# filament.net
KiCad netlist of a schematic drawn in EAGLE
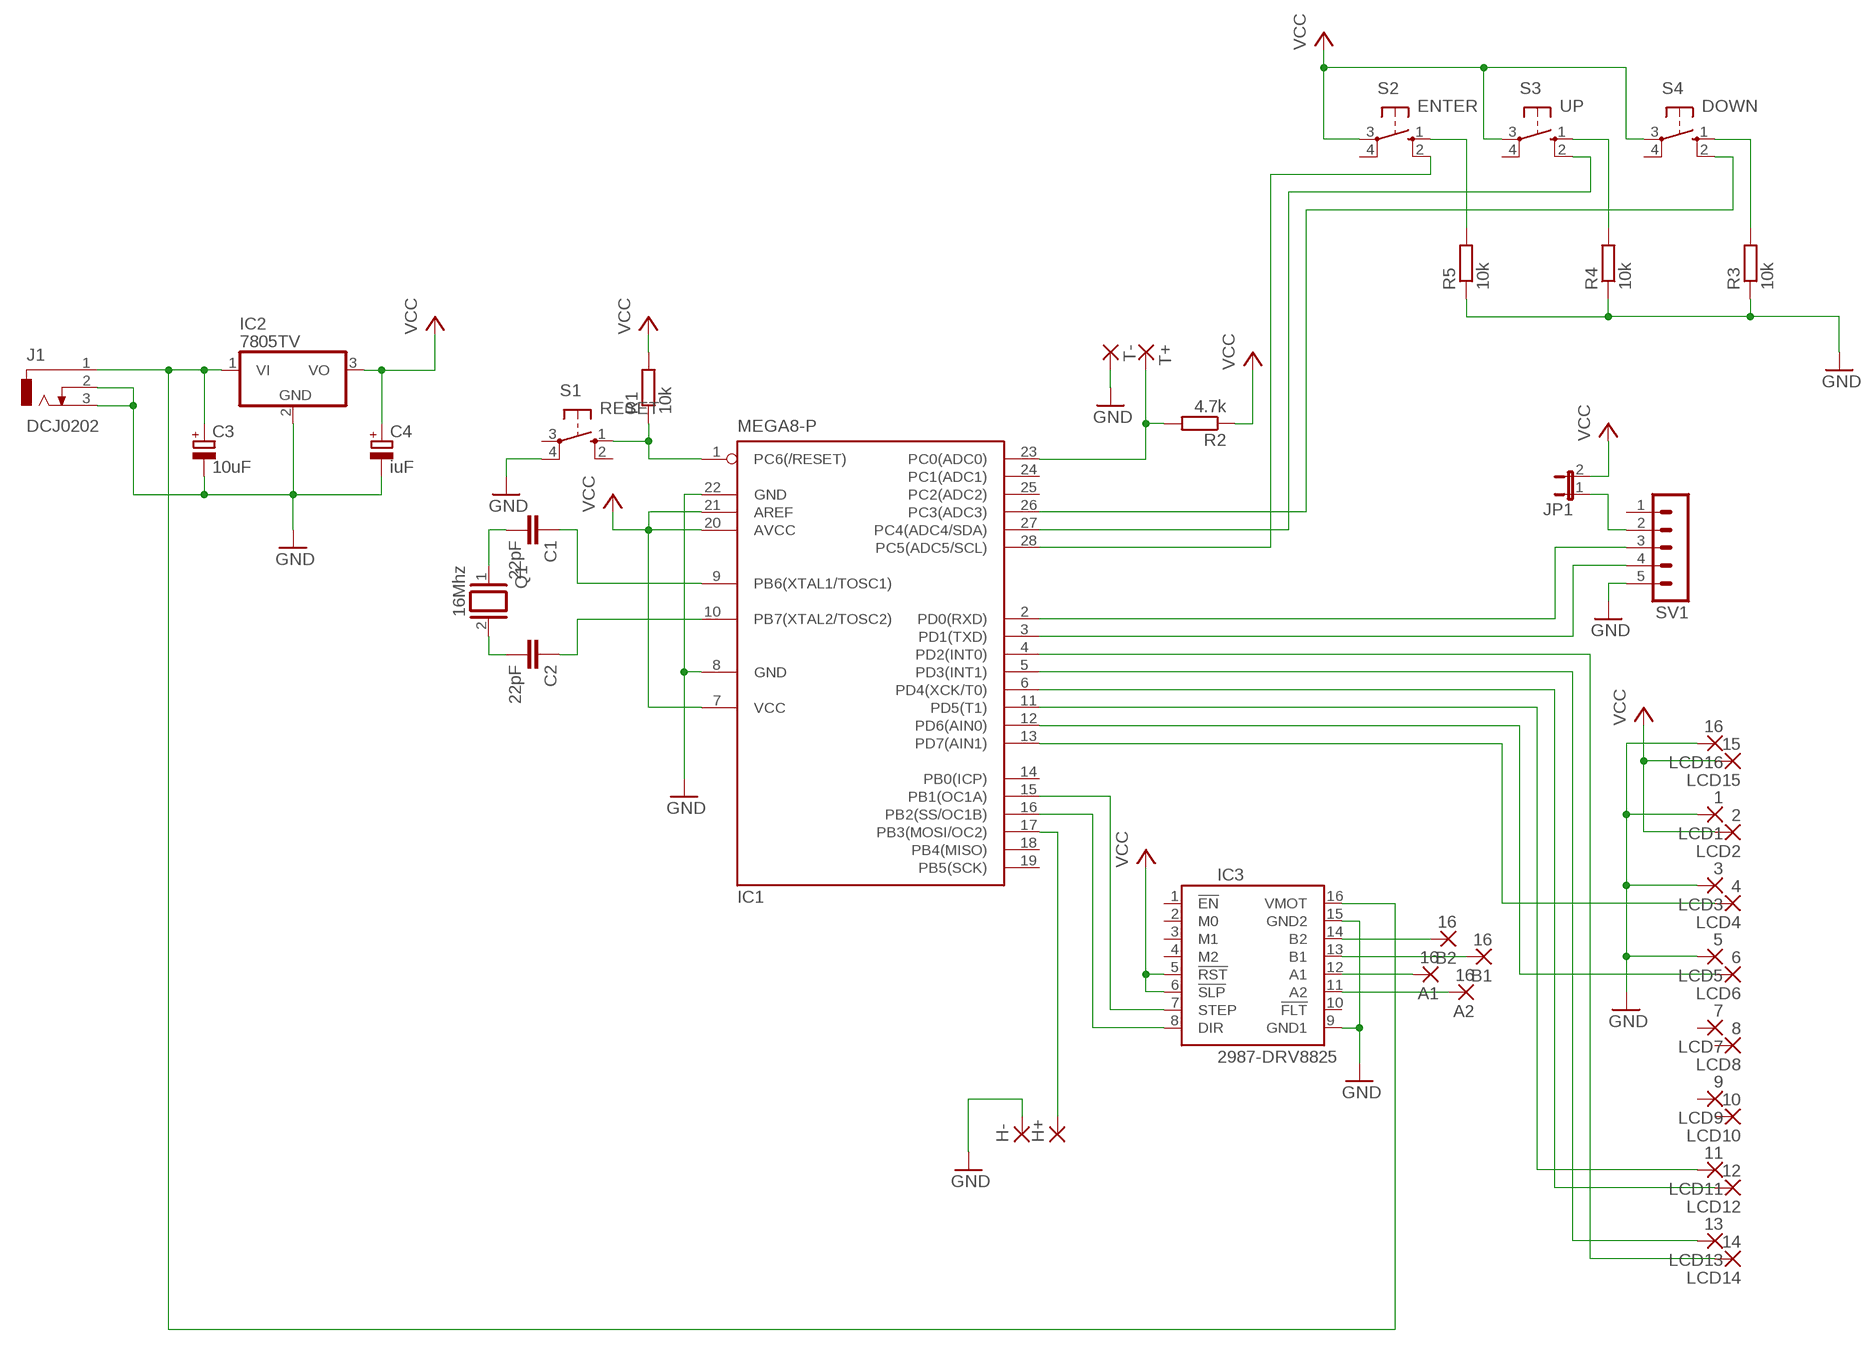
[diagram p0: schematic, sheet 1]

(export (version "E")
  (design (tool "Eeschema 10.0.6"))
  (components
    (comp (ref "A1")
      (value "16")
      (footprint "eagle-import:1,6_0,8")
      (libsource (lib "eagle-import") (part "1,6/0,8"))
    )
    (comp (ref "A2")
      (value "16")
      (footprint "eagle-import:1,6_0,8")
      (libsource (lib "eagle-import") (part "1,6/0,8"))
    )
    (comp (ref "B1")
      (value "16")
      (footprint "eagle-import:1,6_0,8")
      (libsource (lib "eagle-import") (part "1,6/0,8"))
    )
    (comp (ref "B2")
      (value "16")
      (footprint "eagle-import:1,6_0,8")
      (libsource (lib "eagle-import") (part "1,6/0,8"))
    )
    (comp (ref "C1")
      (value "22pF")
      (footprint "eagle-import:C050-025X075")
      (libsource (lib "eagle-import") (part "C-EU050-025X075"))
    )
    (comp (ref "C2")
      (value "22pF")
      (footprint "eagle-import:C050-025X075")
      (libsource (lib "eagle-import") (part "C-EU050-025X075"))
    )
    (comp (ref "C3")
      (value "10uF")
      (footprint "eagle-import:E2-5")
      (libsource (lib "eagle-import") (part "CPOL-EUE2-5"))
    )
    (comp (ref "C4")
      (value "iuF")
      (footprint "eagle-import:E2-5")
      (libsource (lib "eagle-import") (part "CPOL-EUE2-5"))
    )
    (comp (ref "H+")
      (value "1,6/0,8")
      (footprint "eagle-import:1,6_0,8")
      (libsource (lib "eagle-import") (part "1,6/0,8"))
    )
    (comp (ref "H-")
      (value "1,6/0,8")
      (footprint "eagle-import:1,6_0,8")
      (libsource (lib "eagle-import") (part "1,6/0,8"))
    )
    (comp (ref "IC1")
      (value "MEGA8-P")
      (footprint "eagle-import:DIL28-3")
      (libsource (lib "eagle-import") (part "MEGA8-P"))
    )
    (comp (ref "IC2")
      (value "7805TV")
      (footprint "eagle-import:TO220V")
      (libsource (lib "eagle-import") (part "78TV05"))
    )
    (comp (ref "IC3")
      (value "2987-DRV8825")
      (footprint "eagle-import:DRV8825")
      (libsource (lib "eagle-import") (part "2987-DRV8825"))
    )
    (comp (ref "J1")
      (value "DCJ0202")
      (footprint "eagle-import:DCJ0202")
      (libsource (lib "eagle-import") (part "DCJ0202"))
    )
    (comp (ref "JP1")
      (value "JP1E")
      (footprint "eagle-import:JP1")
      (libsource (lib "eagle-import") (part "JP1E"))
    )
    (comp (ref "LCD1")
      (value "1")
      (footprint "eagle-import:1,6_0,8")
      (libsource (lib "eagle-import") (part "1,6/0,8"))
    )
    (comp (ref "LCD2")
      (value "2")
      (footprint "eagle-import:1,6_0,8")
      (libsource (lib "eagle-import") (part "1,6/0,8"))
    )
    (comp (ref "LCD3")
      (value "3")
      (footprint "eagle-import:1,6_0,8")
      (libsource (lib "eagle-import") (part "1,6/0,8"))
    )
    (comp (ref "LCD4")
      (value "4")
      (footprint "eagle-import:1,6_0,8")
      (libsource (lib "eagle-import") (part "1,6/0,8"))
    )
    (comp (ref "LCD5")
      (value "5")
      (footprint "eagle-import:1,6_0,8")
      (libsource (lib "eagle-import") (part "1,6/0,8"))
    )
    (comp (ref "LCD6")
      (value "6")
      (footprint "eagle-import:1,6_0,8")
      (libsource (lib "eagle-import") (part "1,6/0,8"))
    )
    (comp (ref "LCD7")
      (value "7")
      (footprint "eagle-import:1,6_0,8")
      (libsource (lib "eagle-import") (part "1,6/0,8"))
    )
    (comp (ref "LCD8")
      (value "8")
      (footprint "eagle-import:1,6_0,8")
      (libsource (lib "eagle-import") (part "1,6/0,8"))
    )
    (comp (ref "LCD9")
      (value "9")
      (footprint "eagle-import:1,6_0,8")
      (libsource (lib "eagle-import") (part "1,6/0,8"))
    )
    (comp (ref "LCD10")
      (value "10")
      (footprint "eagle-import:1,6_0,8")
      (libsource (lib "eagle-import") (part "1,6/0,8"))
    )
    (comp (ref "LCD11")
      (value "11")
      (footprint "eagle-import:1,6_0,8")
      (libsource (lib "eagle-import") (part "1,6/0,8"))
    )
    (comp (ref "LCD12")
      (value "12")
      (footprint "eagle-import:1,6_0,8")
      (libsource (lib "eagle-import") (part "1,6/0,8"))
    )
    (comp (ref "LCD13")
      (value "13")
      (footprint "eagle-import:1,6_0,8")
      (libsource (lib "eagle-import") (part "1,6/0,8"))
    )
    (comp (ref "LCD14")
      (value "14")
      (footprint "eagle-import:1,6_0,8")
      (libsource (lib "eagle-import") (part "1,6/0,8"))
    )
    (comp (ref "LCD15")
      (value "15")
      (footprint "eagle-import:1,6_0,8")
      (libsource (lib "eagle-import") (part "1,6/0,8"))
    )
    (comp (ref "LCD16")
      (value "16")
      (footprint "eagle-import:1,6_0,8")
      (libsource (lib "eagle-import") (part "1,6/0,8"))
    )
    (comp (ref "Q1")
      (value "16Mhz")
      (footprint "eagle-import:QS")
      (libsource (lib "eagle-import") (part "XTAL/S"))
    )
    (comp (ref "R1")
      (value "10k")
      (footprint "eagle-import:0207_10")
      (libsource (lib "eagle-import") (part "R-EU_0207/10"))
    )
    (comp (ref "R2")
      (value "4.7k")
      (footprint "eagle-import:0207_10")
      (libsource (lib "eagle-import") (part "R-EU_0207/10"))
    )
    (comp (ref "R3")
      (value "10k")
      (footprint "eagle-import:0207_10")
      (libsource (lib "eagle-import") (part "R-EU_0207/10"))
    )
    (comp (ref "R4")
      (value "10k")
      (footprint "eagle-import:0207_10")
      (libsource (lib "eagle-import") (part "R-EU_0207/10"))
    )
    (comp (ref "R5")
      (value "10k")
      (footprint "eagle-import:0207_10")
      (libsource (lib "eagle-import") (part "R-EU_0207/10"))
    )
    (comp (ref "S1")
      (value "RESET")
      (footprint "eagle-import:B3F-10XX")
      (libsource (lib "eagle-import") (part "10-XX"))
    )
    (comp (ref "S2")
      (value "ENTER")
      (footprint "eagle-import:B3F-10XX")
      (libsource (lib "eagle-import") (part "10-XX"))
    )
    (comp (ref "S3")
      (value "UP")
      (footprint "eagle-import:B3F-10XX")
      (libsource (lib "eagle-import") (part "10-XX"))
    )
    (comp (ref "S4")
      (value "DOWN")
      (footprint "eagle-import:B3F-10XX")
      (libsource (lib "eagle-import") (part "10-XX"))
    )
    (comp (ref "SV1")
      (value "MA05-1")
      (footprint "eagle-import:MA05-1")
      (libsource (lib "eagle-import") (part "MA05-1"))
    )
    (comp (ref "T+")
      (value "1,6/0,8")
      (footprint "eagle-import:1,6_0,8")
      (libsource (lib "eagle-import") (part "1,6/0,8"))
    )
    (comp (ref "T-")
      (value "1,6/0,8")
      (footprint "eagle-import:1,6_0,8")
      (libsource (lib "eagle-import") (part "1,6/0,8"))
    )
  )
  (nets
    (net (code "1") (name "GND") (class "Default")
      (node (ref "C3") (pin "-") (pinfunction "-_-") (pintype "passive"))
      (node (ref "C4") (pin "-") (pinfunction "-_-") (pintype "passive"))
      (node (ref "H-") (pin "1") (pinfunction "P_1") (pintype "passive"))
      (node (ref "IC1") (pin "22") (pinfunction "GND_22") (pintype "power_in"))
      (node (ref "IC1") (pin "8") (pinfunction "GND_8") (pintype "power_in"))
      (node (ref "IC2") (pin "2") (pinfunction "GND_2") (pintype "passive"))
      (node (ref "IC3") (pin "15") (pinfunction "GND2_15") (pintype "power_in"))
      (node (ref "IC3") (pin "9") (pinfunction "GND1_9") (pintype "power_in"))
      (node (ref "J1") (pin "2") (pinfunction "2_2") (pintype "passive"))
      (node (ref "J1") (pin "3") (pinfunction "3_3") (pintype "passive"))
      (node (ref "LCD1") (pin "1") (pinfunction "P_1") (pintype "passive"))
      (node (ref "LCD16") (pin "1") (pinfunction "P_1") (pintype "passive"))
      (node (ref "LCD3") (pin "1") (pinfunction "P_1") (pintype "passive"))
      (node (ref "LCD5") (pin "1") (pinfunction "P_1") (pintype "passive"))
      (node (ref "R3") (pin "1") (pinfunction "1_1") (pintype "passive"))
      (node (ref "R4") (pin "1") (pinfunction "1_1") (pintype "passive"))
      (node (ref "R5") (pin "1") (pinfunction "1_1") (pintype "passive"))
      (node (ref "S1") (pin "4") (pinfunction "P1_4") (pintype "passive"))
      (node (ref "SV1") (pin "5") (pinfunction "5_5") (pintype "passive"))
      (node (ref "T-") (pin "1") (pinfunction "P_1") (pintype "passive"))
    )
    (net (code "2") (name "Net-(A1-P)") (class "Default")
      (node (ref "A1") (pin "1") (pinfunction "P_1") (pintype "passive"))
      (node (ref "IC3") (pin "12") (pinfunction "A1_12") (pintype "output"))
    )
    (net (code "3") (name "Net-(A2-P)") (class "Default")
      (node (ref "A2") (pin "1") (pinfunction "P_1") (pintype "passive"))
      (node (ref "IC3") (pin "11") (pinfunction "A2_11") (pintype "output"))
    )
    (net (code "4") (name "Net-(B1-P)") (class "Default")
      (node (ref "B1") (pin "1") (pinfunction "P_1") (pintype "passive"))
      (node (ref "IC3") (pin "13") (pinfunction "B1_13") (pintype "output"))
    )
    (net (code "5") (name "Net-(B2-P)") (class "Default")
      (node (ref "B2") (pin "1") (pinfunction "P_1") (pintype "passive"))
      (node (ref "IC3") (pin "14") (pinfunction "B2_14") (pintype "output"))
    )
    (net (code "6") (name "Net-(C1-Pad2)") (class "Default")
      (node (ref "C1") (pin "2") (pinfunction "2_2") (pintype "passive"))
      (node (ref "Q1") (pin "1") (pinfunction "1_1") (pintype "passive"))
    )
    (net (code "7") (name "Net-(C2-Pad2)") (class "Default")
      (node (ref "C2") (pin "2") (pinfunction "2_2") (pintype "passive"))
      (node (ref "Q1") (pin "2") (pinfunction "2_2") (pintype "passive"))
    )
    (net (code "8") (name "Net-(H+-P)") (class "Default")
      (node (ref "H+") (pin "1") (pinfunction "P_1") (pintype "passive"))
      (node (ref "IC1") (pin "17") (pinfunction "PB3(MOSI/OC2)_17") (pintype "bidirectional"))
    )
    (net (code "9") (name "Net-(IC1-PB1(OC1A))") (class "Default")
      (node (ref "IC1") (pin "15") (pinfunction "PB1(OC1A)_15") (pintype "bidirectional"))
      (node (ref "IC3") (pin "7") (pinfunction "STEP_7") (pintype "input"))
    )
    (net (code "10") (name "Net-(IC1-PB2(SS{slash}OC1B))") (class "Default")
      (node (ref "IC1") (pin "16") (pinfunction "PB2(SS/OC1B)_16") (pintype "bidirectional"))
      (node (ref "IC3") (pin "8") (pinfunction "DIR_8") (pintype "input"))
    )
    (net (code "11") (name "Net-(IC1-PB6(XTAL1{slash}TOSC1))") (class "Default")
      (node (ref "C1") (pin "1") (pinfunction "1_1") (pintype "passive"))
      (node (ref "IC1") (pin "9") (pinfunction "PB6(XTAL1/TOSC1)_9") (pintype "bidirectional"))
    )
    (net (code "12") (name "Net-(IC1-PB7(XTAL2{slash}TOSC2))") (class "Default")
      (node (ref "C2") (pin "1") (pinfunction "1_1") (pintype "passive"))
      (node (ref "IC1") (pin "10") (pinfunction "PB7(XTAL2/TOSC2)_10") (pintype "bidirectional"))
    )
    (net (code "13") (name "Net-(IC1-PC0(ADC0))") (class "Default")
      (node (ref "IC1") (pin "23") (pinfunction "PC0(ADC0)_23") (pintype "bidirectional"))
      (node (ref "R2") (pin "2") (pinfunction "2_2") (pintype "passive"))
      (node (ref "T+") (pin "1") (pinfunction "P_1") (pintype "passive"))
    )
    (net (code "14") (name "Net-(IC1-PC3(ADC3))") (class "Default")
      (node (ref "IC1") (pin "26") (pinfunction "PC3(ADC3)_26") (pintype "bidirectional"))
      (node (ref "S4") (pin "2") (pinfunction "S1_2") (pintype "passive"))
    )
    (net (code "15") (name "Net-(IC1-PC4(ADC4{slash}SDA))") (class "Default")
      (node (ref "IC1") (pin "27") (pinfunction "PC4(ADC4/SDA)_27") (pintype "bidirectional"))
      (node (ref "S3") (pin "2") (pinfunction "S1_2") (pintype "passive"))
    )
    (net (code "16") (name "Net-(IC1-PC5(ADC5{slash}SCL))") (class "Default")
      (node (ref "IC1") (pin "28") (pinfunction "PC5(ADC5/SCL)_28") (pintype "bidirectional"))
      (node (ref "S2") (pin "2") (pinfunction "S1_2") (pintype "passive"))
    )
    (net (code "17") (name "Net-(IC1-PC6({slash}RESET))") (class "Default")
      (node (ref "IC1") (pin "1") (pinfunction "PC6(/RESET)_1") (pintype "bidirectional"))
      (node (ref "R1") (pin "1") (pinfunction "1_1") (pintype "passive"))
      (node (ref "S1") (pin "1") (pinfunction "S_1") (pintype "passive"))
    )
    (net (code "18") (name "Net-(IC1-PD0(RXD))") (class "Default")
      (node (ref "IC1") (pin "2") (pinfunction "PD0(RXD)_2") (pintype "bidirectional"))
      (node (ref "SV1") (pin "3") (pinfunction "3_3") (pintype "passive"))
    )
    (net (code "19") (name "Net-(IC1-PD1(TXD))") (class "Default")
      (node (ref "IC1") (pin "3") (pinfunction "PD1(TXD)_3") (pintype "bidirectional"))
      (node (ref "SV1") (pin "4") (pinfunction "4_4") (pintype "passive"))
    )
    (net (code "20") (name "Net-(IC1-PD2(INT0))") (class "Default")
      (node (ref "IC1") (pin "4") (pinfunction "PD2(INT0)_4") (pintype "bidirectional"))
      (node (ref "LCD14") (pin "1") (pinfunction "P_1") (pintype "passive"))
    )
    (net (code "21") (name "Net-(IC1-PD3(INT1))") (class "Default")
      (node (ref "IC1") (pin "5") (pinfunction "PD3(INT1)_5") (pintype "bidirectional"))
      (node (ref "LCD13") (pin "1") (pinfunction "P_1") (pintype "passive"))
    )
    (net (code "22") (name "Net-(IC1-PD4(XCK{slash}T0))") (class "Default")
      (node (ref "IC1") (pin "6") (pinfunction "PD4(XCK/T0)_6") (pintype "bidirectional"))
      (node (ref "LCD12") (pin "1") (pinfunction "P_1") (pintype "passive"))
    )
    (net (code "23") (name "Net-(IC1-PD5(T1))") (class "Default")
      (node (ref "IC1") (pin "11") (pinfunction "PD5(T1)_11") (pintype "bidirectional"))
      (node (ref "LCD11") (pin "1") (pinfunction "P_1") (pintype "passive"))
    )
    (net (code "24") (name "Net-(IC1-PD6(AIN0))") (class "Default")
      (node (ref "IC1") (pin "12") (pinfunction "PD6(AIN0)_12") (pintype "bidirectional"))
      (node (ref "LCD6") (pin "1") (pinfunction "P_1") (pintype "passive"))
    )
    (net (code "25") (name "Net-(IC1-PD7(AIN1))") (class "Default")
      (node (ref "IC1") (pin "13") (pinfunction "PD7(AIN1)_13") (pintype "bidirectional"))
      (node (ref "LCD4") (pin "1") (pinfunction "P_1") (pintype "passive"))
    )
    (net (code "26") (name "Net-(IC2-VI)") (class "Default")
      (node (ref "C3") (pin "+") (pinfunction "+_+") (pintype "passive"))
      (node (ref "IC2") (pin "1") (pinfunction "VI_1") (pintype "input"))
      (node (ref "IC3") (pin "16") (pinfunction "VMOT_16") (pintype "power_in"))
      (node (ref "J1") (pin "1") (pinfunction "1_1") (pintype "passive"))
    )
    (net (code "27") (name "Net-(JP1-Pad1)") (class "Default")
      (node (ref "JP1") (pin "1") (pinfunction "1_1") (pintype "passive"))
      (node (ref "SV1") (pin "2") (pinfunction "2_2") (pintype "passive"))
    )
    (net (code "28") (name "Net-(S2-S)") (class "Default")
      (node (ref "R5") (pin "2") (pinfunction "2_2") (pintype "passive"))
      (node (ref "S2") (pin "1") (pinfunction "S_1") (pintype "passive"))
    )
    (net (code "29") (name "Net-(S3-S)") (class "Default")
      (node (ref "R4") (pin "2") (pinfunction "2_2") (pintype "passive"))
      (node (ref "S3") (pin "1") (pinfunction "S_1") (pintype "passive"))
    )
    (net (code "30") (name "Net-(S4-S)") (class "Default")
      (node (ref "R3") (pin "2") (pinfunction "2_2") (pintype "passive"))
      (node (ref "S4") (pin "1") (pinfunction "S_1") (pintype "passive"))
    )
    (net (code "31") (name "VCC") (class "Default")
      (node (ref "C4") (pin "+") (pinfunction "+_+") (pintype "passive"))
      (node (ref "IC1") (pin "20") (pinfunction "AVCC_20") (pintype "power_in"))
      (node (ref "IC1") (pin "21") (pinfunction "AREF_21") (pintype "passive"))
      (node (ref "IC1") (pin "7") (pinfunction "VCC_7") (pintype "power_in"))
      (node (ref "IC2") (pin "3") (pinfunction "VO_3") (pintype "passive"))
      (node (ref "IC3") (pin "5") (pinfunction "~{RST}_5") (pintype "input"))
      (node (ref "IC3") (pin "6") (pinfunction "~{SLP}_6") (pintype "input"))
      (node (ref "JP1") (pin "2") (pinfunction "2_2") (pintype "passive"))
      (node (ref "LCD15") (pin "1") (pinfunction "P_1") (pintype "passive"))
      (node (ref "LCD2") (pin "1") (pinfunction "P_1") (pintype "passive"))
      (node (ref "R1") (pin "2") (pinfunction "2_2") (pintype "passive"))
      (node (ref "R2") (pin "1") (pinfunction "1_1") (pintype "passive"))
      (node (ref "S2") (pin "3") (pinfunction "P_3") (pintype "passive"))
      (node (ref "S3") (pin "3") (pinfunction "P_3") (pintype "passive"))
      (node (ref "S4") (pin "3") (pinfunction "P_3") (pintype "passive"))
    )
    (net (code "32") (name "unconnected-(IC1-PB0(ICP)-Pad14)") (class "Default")
      (node (ref "IC1") (pin "14") (pinfunction "PB0(ICP)_14") (pintype "bidirectional"))
    )
    (net (code "33") (name "unconnected-(IC1-PB4(MISO)-Pad18)") (class "Default")
      (node (ref "IC1") (pin "18") (pinfunction "PB4(MISO)_18") (pintype "bidirectional"))
    )
    (net (code "34") (name "unconnected-(IC1-PB5(SCK)-Pad19)") (class "Default")
      (node (ref "IC1") (pin "19") (pinfunction "PB5(SCK)_19") (pintype "bidirectional"))
    )
    (net (code "35") (name "unconnected-(IC1-PC1(ADC1)-Pad24)") (class "Default")
      (node (ref "IC1") (pin "24") (pinfunction "PC1(ADC1)_24") (pintype "bidirectional"))
    )
    (net (code "36") (name "unconnected-(IC1-PC2(ADC2)-Pad25)") (class "Default")
      (node (ref "IC1") (pin "25") (pinfunction "PC2(ADC2)_25") (pintype "bidirectional"))
    )
    (net (code "37") (name "unconnected-(IC3-M0-Pad2)") (class "Default")
      (node (ref "IC3") (pin "2") (pinfunction "M0_2") (pintype "passive"))
    )
    (net (code "38") (name "unconnected-(IC3-M1-Pad3)") (class "Default")
      (node (ref "IC3") (pin "3") (pinfunction "M1_3") (pintype "passive"))
    )
    (net (code "39") (name "unconnected-(IC3-M2-Pad4)") (class "Default")
      (node (ref "IC3") (pin "4") (pinfunction "M2_4") (pintype "passive"))
    )
    (net (code "40") (name "unconnected-(IC3-~{EN}-Pad1)") (class "Default")
      (node (ref "IC3") (pin "1") (pinfunction "~{EN}_1") (pintype "passive"))
    )
    (net (code "41") (name "unconnected-(IC3-~{FLT}-Pad10)") (class "Default")
      (node (ref "IC3") (pin "10") (pinfunction "~{FLT}_10") (pintype "open_collector"))
    )
    (net (code "42") (name "unconnected-(LCD7-P-Pad1)") (class "Default")
      (node (ref "LCD7") (pin "1") (pinfunction "P_1") (pintype "passive"))
    )
    (net (code "43") (name "unconnected-(LCD8-P-Pad1)") (class "Default")
      (node (ref "LCD8") (pin "1") (pinfunction "P_1") (pintype "passive"))
    )
    (net (code "44") (name "unconnected-(LCD9-P-Pad1)") (class "Default")
      (node (ref "LCD9") (pin "1") (pinfunction "P_1") (pintype "passive"))
    )
    (net (code "45") (name "unconnected-(LCD10-P-Pad1)") (class "Default")
      (node (ref "LCD10") (pin "1") (pinfunction "P_1") (pintype "passive"))
    )
    (net (code "46") (name "unconnected-(S1-P-Pad3)") (class "Default")
      (node (ref "S1") (pin "3") (pinfunction "P_3") (pintype "passive"))
    )
    (net (code "47") (name "unconnected-(S1-S1-Pad2)") (class "Default")
      (node (ref "S1") (pin "2") (pinfunction "S1_2") (pintype "passive"))
    )
    (net (code "48") (name "unconnected-(S2-P1-Pad4)") (class "Default")
      (node (ref "S2") (pin "4") (pinfunction "P1_4") (pintype "passive"))
    )
    (net (code "49") (name "unconnected-(S3-P1-Pad4)") (class "Default")
      (node (ref "S3") (pin "4") (pinfunction "P1_4") (pintype "passive"))
    )
    (net (code "50") (name "unconnected-(S4-P1-Pad4)") (class "Default")
      (node (ref "S4") (pin "4") (pinfunction "P1_4") (pintype "passive"))
    )
    (net (code "51") (name "unconnected-(SV1-Pad1)") (class "Default")
      (node (ref "SV1") (pin "1") (pinfunction "1_1") (pintype "passive"))
    )
  )
)
